# SW_12.net
KiCad netlist of a schematic drawn in Altium Designer
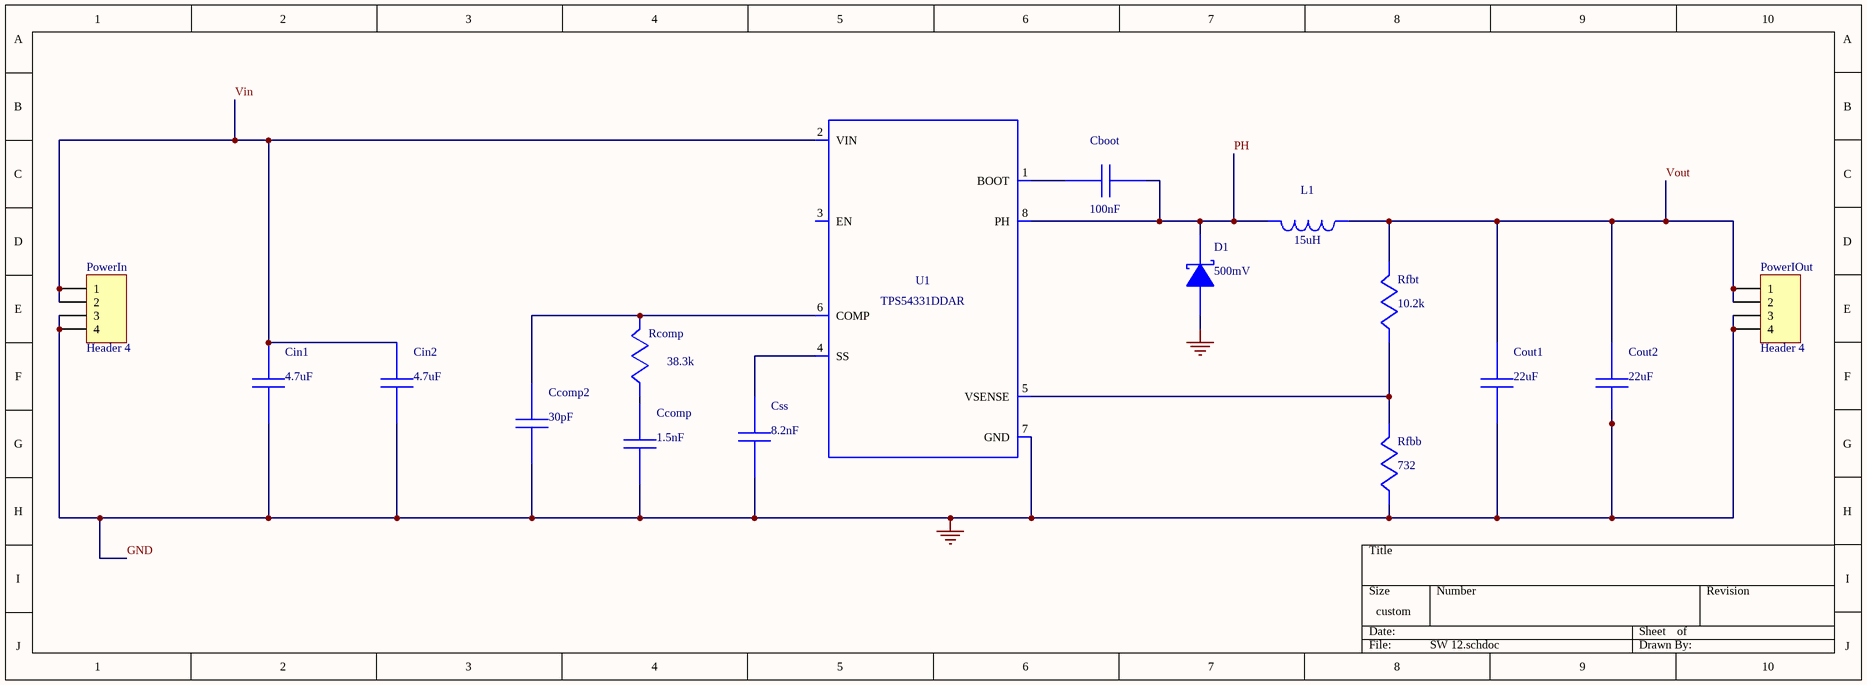
[diagram p0: SW 12.schdoc]

(export (version "E")
  (design (tool "Eeschema 10.0.6"))
  (components
    (comp (ref "Cboot")
      (value "100nF")
      (footprint "1608[0603]")
      (description "C1608X7R1E104K")
      (libsource (lib "TI WEBENCH") (part "Cboot"))
    )
    (comp (ref "Ccomp")
      (value "1.5nF")
      (footprint "6-0805_M")
      (description "CC0805KRX7R9BB15")
      (fields (field (name "MANUFACTURER PART NUMBER") "CC0805KRX7R9BB152"))
      (libsource (lib "TI WEBENCH") (part "Ccomp"))
    )
    (comp (ref "Ccomp2")
      (value "30pF")
      (footprint "6-0805_M")
      (description "CL21C300JBANNNC")
      (libsource (lib "TI WEBENCH") (part "Ccomp2"))
    )
    (comp (ref "Cin1")
      (value "4.7uF")
      (footprint "C1210_M")
      (description "GRM32ER71H475KA8")
      (fields (field (name "MANUFACTURER PART NUMBER") "GRM32ER71H475KA88L"))
      (libsource (lib "TI WEBENCH") (part "Cin"))
    )
    (comp (ref "Cin2")
      (value "4.7uF")
      (footprint "C1210_M")
      (description "GRM32ER71H475KA8")
      (fields (field (name "MANUFACTURER PART NUMBER") "GRM32ER71H475KA88L"))
      (libsource (lib "TI WEBENCH") (part "Cin"))
    )
    (comp (ref "Cout1")
      (value "22uF")
      (footprint "C1210_M")
      (description "GRM32ER61E226KE1")
      (fields (field (name "MANUFACTURER PART NUMBER") "GRM32ER61E226KE15L"))
      (libsource (lib "TI WEBENCH") (part "Cout"))
    )
    (comp (ref "Cout2")
      (value "22uF")
      (footprint "C1210_M")
      (description "GRM32ER61E226KE1")
      (fields (field (name "MANUFACTURER PART NUMBER") "GRM32ER61E226KE15L"))
      (libsource (lib "TI WEBENCH") (part "Cout"))
    )
    (comp (ref "Css")
      (value "8.2nF")
      (footprint "0603")
      (description "GRM188R71E822KA0")
      (fields (field (name "MANUFACTURER PART NUMBER") "GRM188R71E822KA01D"))
      (libsource (lib "TI WEBENCH") (part "Css"))
    )
    (comp (ref "D1")
      (value "500mV")
      (footprint "SMA Diode Package")
      (description "B340A-13-F")
      (libsource (lib "TI WEBENCH") (part "D1"))
    )
    (comp (ref "L1")
      (value "15uH")
      (footprint "SRR1260")
      (description "SRR1260-150M")
      (libsource (lib "TI WEBENCH") (part "L1"))
    )
    (comp (ref "PowerIn")
      (value "Header 4")
      (footprint "HDR1X4")
      (description "Header, 4-Pin")
      (fields (field (name "PUBLISHER") "Altium Limited"))
      (libsource (lib "Miscellaneous Connectors") (part "Header 4"))
    )
    (comp (ref "PowerIOut")
      (value "Header 4")
      (footprint "HDR1X4")
      (description "Header, 4-Pin")
      (fields (field (name "PUBLISHER") "Altium Limited"))
      (libsource (lib "Miscellaneous Connectors") (part "Header 4"))
    )
    (comp (ref "Rcomp")
      (value "38.3k")
      (footprint "6-0805_M")
      (description "CRCW080538K3FKEA")
      (libsource (lib "TI WEBENCH") (part "Rcomp"))
    )
    (comp (ref "Rfbb")
      (value "732")
      (footprint "6-0805_M")
      (description "CRCW0805732RFKEA")
      (libsource (lib "TI WEBENCH") (part "Rfbb"))
    )
    (comp (ref "Rfbt")
      (value "10.2k")
      (footprint "6-0805_M")
      (description "CRCW080510K2FKEA")
      (libsource (lib "TI WEBENCH") (part "Rfbt"))
    )
    (comp (ref "U1")
      (value "TPS54331DDAR")
      (footprint "TI-D8_N")
      (fields (field (name "PACKAGEREFERENCE") "TPS54331DDAR"))
      (libsource (lib "TI WEBENCH") (part "U1"))
    )
  )
  (nets
    (net (code "1") (name "/PH") (class "Default")
      (node (ref "Cboot") (pin "2") (pinfunction "2_2") (pintype "passive"))
      (node (ref "D1") (pin "1") (pinfunction "K_1") (pintype "passive"))
      (node (ref "L1") (pin "1") (pinfunction "1_1") (pintype "passive"))
      (node (ref "U1") (pin "8") (pinfunction "PH_8") (pintype "passive"))
    )
    (net (code "2") (name "/Vin") (class "Default")
      (node (ref "Cin1") (pin "1") (pinfunction "1_1") (pintype "passive"))
      (node (ref "Cin2") (pin "1") (pinfunction "1_1") (pintype "passive"))
      (node (ref "PowerIn") (pin "1") (pinfunction "1_1") (pintype "passive"))
      (node (ref "PowerIn") (pin "2") (pinfunction "2_2") (pintype "passive"))
      (node (ref "U1") (pin "2") (pinfunction "VIN_2") (pintype "passive"))
    )
    (net (code "3") (name "/Vout") (class "Default")
      (node (ref "Cout1") (pin "1") (pinfunction "1_1") (pintype "passive"))
      (node (ref "Cout2") (pin "1") (pinfunction "1_1") (pintype "passive"))
      (node (ref "L1") (pin "2") (pinfunction "2_2") (pintype "passive"))
      (node (ref "PowerIOut") (pin "1") (pinfunction "1_1") (pintype "passive"))
      (node (ref "PowerIOut") (pin "2") (pinfunction "2_2") (pintype "passive"))
      (node (ref "Rfbt") (pin "1") (pinfunction "1_1") (pintype "passive"))
    )
    (net (code "4") (name "0") (class "Default")
      (node (ref "Ccomp") (pin "2") (pinfunction "2_2") (pintype "passive"))
      (node (ref "Ccomp2") (pin "2") (pinfunction "2_2") (pintype "passive"))
      (node (ref "Cin1") (pin "2") (pinfunction "2_2") (pintype "passive"))
      (node (ref "Cin2") (pin "2") (pinfunction "2_2") (pintype "passive"))
      (node (ref "Cout1") (pin "2") (pinfunction "2_2") (pintype "passive"))
      (node (ref "Cout2") (pin "2") (pinfunction "2_2") (pintype "passive"))
      (node (ref "Css") (pin "2") (pinfunction "2_2") (pintype "passive"))
      (node (ref "D1") (pin "2") (pinfunction "A_2") (pintype "passive"))
      (node (ref "PowerIOut") (pin "3") (pinfunction "3_3") (pintype "passive"))
      (node (ref "PowerIOut") (pin "4") (pinfunction "4_4") (pintype "passive"))
      (node (ref "PowerIn") (pin "3") (pinfunction "3_3") (pintype "passive"))
      (node (ref "PowerIn") (pin "4") (pinfunction "4_4") (pintype "passive"))
      (node (ref "Rfbb") (pin "2") (pinfunction "2_2") (pintype "passive"))
      (node (ref "U1") (pin "7") (pinfunction "GND_7") (pintype "passive"))
    )
    (net (code "5") (name "Net-(Ccomp-Pad1)") (class "Default")
      (node (ref "Ccomp") (pin "1") (pinfunction "1_1") (pintype "passive"))
      (node (ref "Rcomp") (pin "2") (pinfunction "2_2") (pintype "passive"))
    )
    (net (code "6") (name "Net-(U1-BOOT)") (class "Default")
      (node (ref "Cboot") (pin "1") (pinfunction "1_1") (pintype "passive"))
      (node (ref "U1") (pin "1") (pinfunction "BOOT_1") (pintype "passive"))
    )
    (net (code "7") (name "Net-(U1-COMP)") (class "Default")
      (node (ref "Ccomp2") (pin "1") (pinfunction "1_1") (pintype "passive"))
      (node (ref "Rcomp") (pin "1") (pinfunction "1_1") (pintype "passive"))
      (node (ref "U1") (pin "6") (pinfunction "COMP_6") (pintype "passive"))
    )
    (net (code "8") (name "Net-(U1-SS)") (class "Default")
      (node (ref "Css") (pin "1") (pinfunction "1_1") (pintype "passive"))
      (node (ref "U1") (pin "4") (pinfunction "SS_4") (pintype "passive"))
    )
    (net (code "9") (name "Net-(U1-VSENSE)") (class "Default")
      (node (ref "Rfbb") (pin "1") (pinfunction "1_1") (pintype "passive"))
      (node (ref "Rfbt") (pin "2") (pinfunction "2_2") (pintype "passive"))
      (node (ref "U1") (pin "5") (pinfunction "VSENSE_5") (pintype "passive"))
    )
    (net (code "10") (name "unconnected-(U1-EN-Pad3)") (class "Default")
      (node (ref "U1") (pin "3") (pinfunction "EN_3") (pintype "passive"))
    )
  )
)
